# USB_Charge.net
KiCad netlist of a schematic drawn in Altium Designer
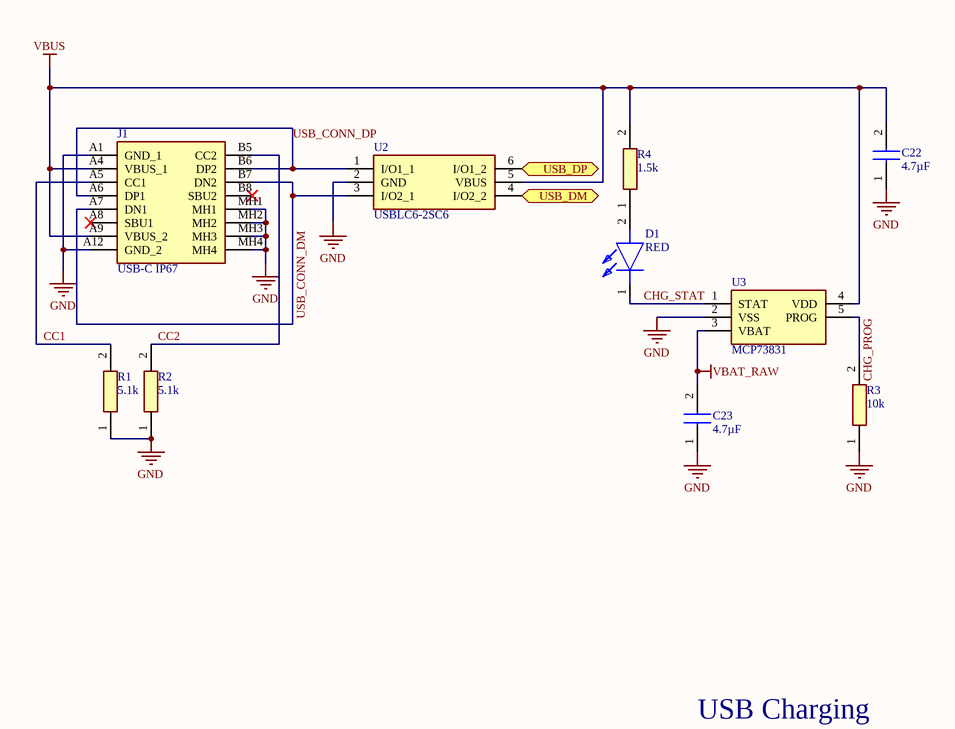
[diagram p0: USB_Charge.SchDoc]

(export (version "E")
  (design (tool "Eeschema 10.0.6"))
  (components
    (comp (ref "C22")
      (value "4.7µF")
      (footprint "BoatRC:GRM18x")
      (description "4.7 µF X7R ±10% 16 V")
      (fields (field (name "MANUFACTURER_PART_NUMBER") "GRM188Z71C475KE21D"))
      (libsource (lib "BoatRC") (part "C_4u7F_0603_X7R_16V"))
    )
    (comp (ref "C23")
      (value "4.7µF")
      (footprint "BoatRC:GRM18x")
      (description "4.7 µF X7R ±10% 16 V")
      (fields (field (name "MANUFACTURER_PART_NUMBER") "GRM188Z71C475KE21D"))
      (libsource (lib "BoatRC") (part "C_4u7F_0603_X7R_16V"))
    )
    (comp (ref "D1")
      (value "RED")
      (footprint "BoatRC:LEDC1608X55N")
      (description "Red LED 631 nm 54 mcd water clear")
      (fields (field (name "MANUFACTURER_PART_NUMBER") "LTST-C191KRKT"))
      (libsource (lib "BoatRC") (part "LED_Red_0603"))
    )
    (comp (ref "J1")
      (value "USB-C IP67")
      (footprint "BoatRC:USB4730GFAKIT")
      (description "USB-C receptacle, USB 2.0, 16-pin, top-mount SMT, IP67 with USBTJ-04 gasket")
      (fields (field (name "MANUFACTURER_PART_NUMBER") "USB4730-GF-A-KIT"))
      (libsource (lib "BoatRC") (part "USB4730-GF-A-KIT"))
    )
    (comp (ref "R1")
      (value "5.1k")
      (footprint "BoatRC:RESC1005X35N")
      (description "5.1 kΩ thin film ±0.1% 25 ppm")
      (fields (field (name "MANUFACTURER_PART_NUMBER") "RT0402BRD075K1L"))
      (libsource (lib "BoatRC") (part "R_5k1_0402_0p1pct"))
    )
    (comp (ref "R2")
      (value "5.1k")
      (footprint "BoatRC:RESC1005X35N")
      (description "5.1 kΩ thin film ±0.1% 25 ppm")
      (fields (field (name "MANUFACTURER_PART_NUMBER") "RT0402BRD075K1L"))
      (libsource (lib "BoatRC") (part "R_5k1_0402_0p1pct"))
    )
    (comp (ref "R3")
      (value "10k")
      (footprint "BoatRC:RESC1005X35N")
      (description "10 kΩ thin film ±0.1% 25 ppm")
      (fields (field (name "MANUFACTURER_PART_NUMBER") "RT0402BRD0710KL"))
      (libsource (lib "BoatRC") (part "R_10k_0402_0p1pct"))
    )
    (comp (ref "R4")
      (value "1.5k")
      (footprint "BoatRC:RESC1005X35N")
      (description "1.5 kΩ thin film ±0.1% 25 ppm")
      (fields (field (name "MANUFACTURER_PART_NUMBER") "RT0402BRD071K5L"))
      (libsource (lib "BoatRC") (part "R_1k5_0402_0p1pct"))
    )
    (comp (ref "U2")
      (value "USBLC6-2SC6")
      (footprint "BoatRC:SOT95P280X145-6N")
      (description "USB 2.0 ESD 2-line + VBUS")
      (libsource (lib "BoatRC") (part "USBLC6-2SC6"))
    )
    (comp (ref "U3")
      (value "MCP73831")
      (footprint "BoatRC:SOT95P270X145-5N")
      (description "LiPo linear charger 4.20 V 500 mA max")
      (fields (field (name "MANUFACTURER_PART_NUMBER") "MCP73831T-2ACI/OT"))
      (libsource (lib "BoatRC") (part "MCP73831T-2ACI_OT"))
    )
  )
  (nets
    (net (code "1") (name "/CC1") (class "Default")
      (node (ref "J1") (pin "A5") (pinfunction "CC1_A5") (pintype "passive"))
      (node (ref "R1") (pin "2") (pinfunction "2_2") (pintype "passive"))
    )
    (net (code "2") (name "/CC2") (class "Default")
      (node (ref "J1") (pin "B5") (pinfunction "CC2_B5") (pintype "passive"))
      (node (ref "R2") (pin "2") (pinfunction "2_2") (pintype "passive"))
    )
    (net (code "3") (name "/CHG_PROG") (class "Default")
      (node (ref "R3") (pin "2") (pinfunction "2_2") (pintype "passive"))
      (node (ref "U3") (pin "5") (pinfunction "PROG_5") (pintype "passive"))
    )
    (net (code "4") (name "/CHG_STAT") (class "Default")
      (node (ref "D1") (pin "1") (pinfunction "K_1") (pintype "passive"))
      (node (ref "U3") (pin "1") (pinfunction "STAT_1") (pintype "passive"))
    )
    (net (code "5") (name "/USB_CONN_DM") (class "Default")
      (node (ref "J1") (pin "A7") (pinfunction "DN1_A7") (pintype "passive"))
      (node (ref "J1") (pin "B7") (pinfunction "DN2_B7") (pintype "passive"))
      (node (ref "U2") (pin "3") (pinfunction "I/O2_1_3") (pintype "passive"))
    )
    (net (code "6") (name "/USB_CONN_DP") (class "Default")
      (node (ref "J1") (pin "A6") (pinfunction "DP1_A6") (pintype "passive"))
      (node (ref "J1") (pin "B6") (pinfunction "DP2_B6") (pintype "passive"))
      (node (ref "U2") (pin "1") (pinfunction "I/O1_1_1") (pintype "passive"))
    )
    (net (code "7") (name "/USB_DM") (class "Default")
      (node (ref "U2") (pin "4") (pinfunction "I/O2_2_4") (pintype "passive"))
    )
    (net (code "8") (name "/USB_DP") (class "Default")
      (node (ref "U2") (pin "6") (pinfunction "I/O1_2_6") (pintype "passive"))
    )
    (net (code "9") (name "GND") (class "Default")
      (node (ref "C22") (pin "1") (pinfunction "1_1") (pintype "passive"))
      (node (ref "C23") (pin "1") (pinfunction "1_1") (pintype "passive"))
      (node (ref "J1") (pin "A1") (pinfunction "GND_1_A1") (pintype "passive"))
      (node (ref "J1") (pin "A12") (pinfunction "GND_2_A12") (pintype "passive"))
      (node (ref "J1") (pin "MH1") (pinfunction "MH1_MH1") (pintype "passive"))
      (node (ref "J1") (pin "MH2") (pinfunction "MH2_MH2") (pintype "passive"))
      (node (ref "J1") (pin "MH3") (pinfunction "MH3_MH3") (pintype "passive"))
      (node (ref "J1") (pin "MH4") (pinfunction "MH4_MH4") (pintype "passive"))
      (node (ref "R1") (pin "1") (pinfunction "1_1") (pintype "passive"))
      (node (ref "R2") (pin "1") (pinfunction "1_1") (pintype "passive"))
      (node (ref "R3") (pin "1") (pinfunction "1_1") (pintype "passive"))
      (node (ref "U2") (pin "2") (pinfunction "GND_2") (pintype "passive"))
      (node (ref "U3") (pin "2") (pinfunction "VSS_2") (pintype "passive"))
    )
    (net (code "10") (name "Net-(D1-A)") (class "Default")
      (node (ref "D1") (pin "2") (pinfunction "A_2") (pintype "passive"))
      (node (ref "R4") (pin "1") (pinfunction "1_1") (pintype "passive"))
    )
    (net (code "11") (name "VBAT_RAW") (class "Default")
      (node (ref "C23") (pin "2") (pinfunction "2_2") (pintype "passive"))
      (node (ref "U3") (pin "3") (pinfunction "VBAT_3") (pintype "passive"))
    )
    (net (code "12") (name "VBUS") (class "Default")
      (node (ref "C22") (pin "2") (pinfunction "2_2") (pintype "passive"))
      (node (ref "J1") (pin "A4") (pinfunction "VBUS_1_A4") (pintype "passive"))
      (node (ref "J1") (pin "A9") (pinfunction "VBUS_2_A9") (pintype "passive"))
      (node (ref "R4") (pin "2") (pinfunction "2_2") (pintype "passive"))
      (node (ref "U2") (pin "5") (pinfunction "VBUS_5") (pintype "passive"))
      (node (ref "U3") (pin "4") (pinfunction "VDD_4") (pintype "passive"))
    )
    (net (code "13") (name "unconnected-(J1-SBU1-PadA8)") (class "Default")
      (node (ref "J1") (pin "A8") (pinfunction "SBU1_A8") (pintype "passive+no_connect"))
    )
    (net (code "14") (name "unconnected-(J1-SBU2-PadB8)") (class "Default")
      (node (ref "J1") (pin "B8") (pinfunction "SBU2_B8") (pintype "passive+no_connect"))
    )
  )
)
